# LED_Control.net
KiCad netlist of a schematic drawn in EAGLE
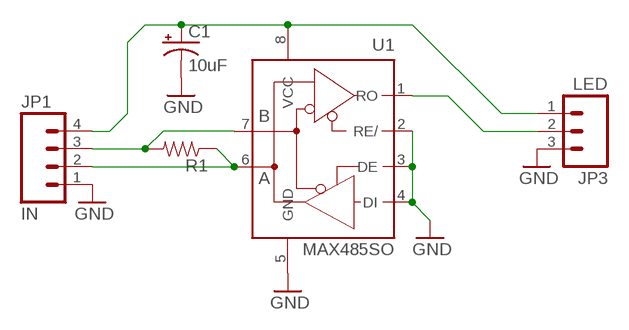
[diagram p0: schematic, sheet 1]

(export (version "E")
  (design (tool "Eeschema 10.0.6"))
  (components
    (comp (ref "C1")
      (value "10uF")
      (footprint "eagle-import:EIA3216")
      (libsource (lib "eagle-import") (part "10UF-16V-10%(TANT)"))
    )
    (comp (ref "JP1")
      (value "IN")
      (footprint "eagle-import:MOLEX-1X4_LOCK")
      (libsource (lib "eagle-import") (part "M04POLAR_LOCK"))
    )
    (comp (ref "JP3")
      (value "LED")
      (footprint "eagle-import:1X03_LOCK")
      (libsource (lib "eagle-import") (part "M03LOCK"))
    )
    (comp (ref "R1")
      (value "RESISTOR0805-RES")
      (footprint "eagle-import:0805")
      (libsource (lib "eagle-import") (part "RESISTOR0805-RES"))
    )
    (comp (ref "U1")
      (value "MAX485SO")
      (footprint "eagle-import:SO08")
      (libsource (lib "eagle-import") (part "MAX485SO"))
    )
  )
  (nets
    (net (code "1") (name "GND") (class "Default")
      (node (ref "C1") (pin "C") (pinfunction "-_C") (pintype "passive"))
      (node (ref "JP1") (pin "1") (pinfunction "1_1") (pintype "passive"))
      (node (ref "JP3") (pin "3") (pinfunction "3_3") (pintype "passive"))
      (node (ref "U1") (pin "2") (pinfunction "RE/_2") (pintype "input"))
      (node (ref "U1") (pin "3") (pinfunction "DE_3") (pintype "input"))
      (node (ref "U1") (pin "4") (pinfunction "DI_4") (pintype "input"))
      (node (ref "U1") (pin "5") (pinfunction "GND_5") (pintype "bidirectional"))
    )
    (net (code "2") (name "Net-(C1-+)") (class "Default")
      (node (ref "C1") (pin "A") (pinfunction "+_A") (pintype "passive"))
      (node (ref "JP1") (pin "4") (pinfunction "4_4") (pintype "passive"))
      (node (ref "JP3") (pin "1") (pinfunction "1_1") (pintype "passive"))
      (node (ref "U1") (pin "8") (pinfunction "VCC_8") (pintype "bidirectional"))
    )
    (net (code "3") (name "Net-(U1-A)") (class "Default")
      (node (ref "JP1") (pin "2") (pinfunction "2_2") (pintype "passive"))
      (node (ref "R1") (pin "1") (pinfunction "1_1") (pintype "passive"))
      (node (ref "U1") (pin "6") (pinfunction "A_6") (pintype "passive"))
    )
    (net (code "4") (name "Net-(U1-B)") (class "Default")
      (node (ref "JP1") (pin "3") (pinfunction "3_3") (pintype "passive"))
      (node (ref "R1") (pin "2") (pinfunction "2_2") (pintype "passive"))
      (node (ref "U1") (pin "7") (pinfunction "B_7") (pintype "passive"))
    )
    (net (code "5") (name "Net-(U1-RO)") (class "Default")
      (node (ref "JP3") (pin "2") (pinfunction "2_2") (pintype "passive"))
      (node (ref "U1") (pin "1") (pinfunction "RO_1") (pintype "output"))
    )
  )
)
